# PSRAM.net
KiCad netlist of a schematic drawn in Altium Designer
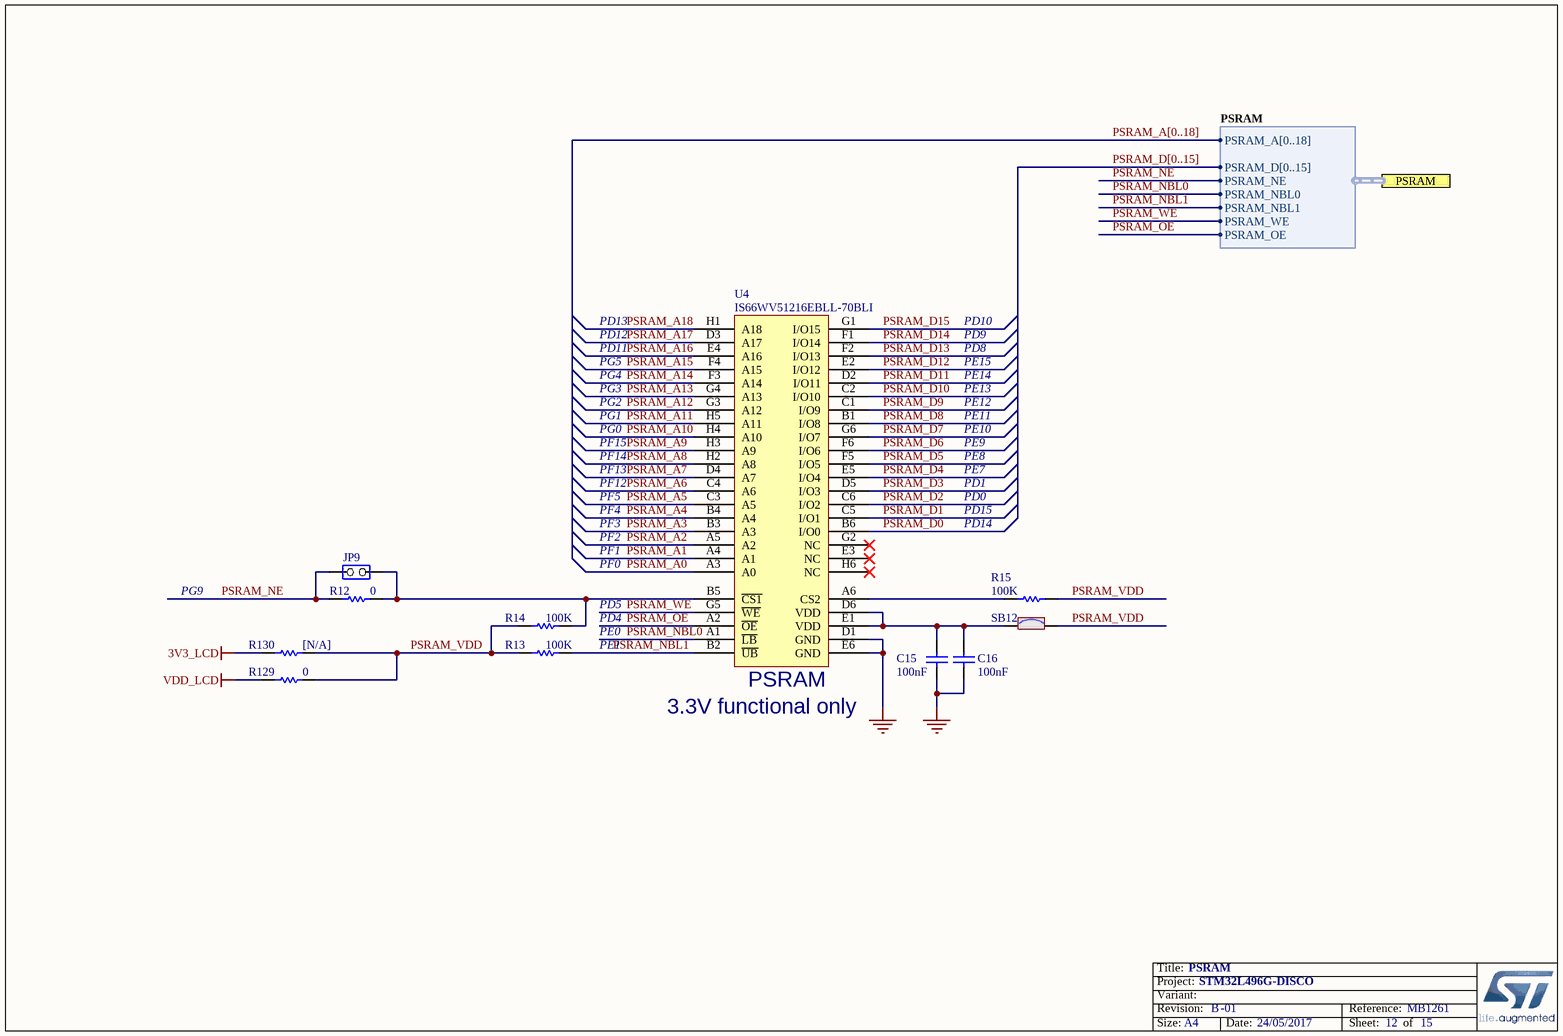
[diagram p0: PSRAM.SchDoc]

(export (version "E")
  (design (tool "Eeschema 10.0.6"))
  (components
    (comp (ref "C15")
      (value "100nF")
      (footprint "0603C")
      (description "Capacitor,100nF,10%,16V,X7R,0603,YAGEO")
      (fields (field (name "Comment") "CC0603KRX7R7BB104") (field (name "PUBLISHER") "Altium Limited"))
      (libsource (lib "Miscellaneous Devices") (part "Cap"))
    )
    (comp (ref "C16")
      (value "100nF")
      (footprint "0603C")
      (description "Capacitor,100nF,10%,16V,X7R,0603,YAGEO")
      (fields (field (name "Comment") "CC0603KRX7R7BB104") (field (name "PUBLISHER") "Altium Limited"))
      (libsource (lib "Miscellaneous Devices") (part "Cap"))
    )
    (comp (ref "JP9") (value "2 PIN Jumper") (footprint "SIP2") (libsource (lib "*") (part "JP2")))
    (comp (ref "R12")
      (value "0")
      (footprint "0603R")
      (description "Resistor, 0 ,0603,1%,YAGEO")
      (fields (field (name "PUBLISHER") "Altium Limited"))
      (libsource (lib "Miscellaneous Devices") (part "res1"))
    )
    (comp (ref "R13")
      (value "100K")
      (footprint "0603R")
      (description "Resistor,100K,0603,1%,YAGEO")
      (fields (field (name "Comment") "RC0603FR-07100KL") (field (name "PUBLISHER") "Altium Limited"))
      (libsource (lib "Miscellaneous Devices") (part "res1"))
    )
    (comp (ref "R14")
      (value "100K")
      (footprint "0603R")
      (description "Resistor,100K,0603,1%,YAGEO")
      (fields (field (name "Comment") "RC0603FR-07100KL") (field (name "PUBLISHER") "Altium Limited"))
      (libsource (lib "Miscellaneous Devices") (part "res1"))
    )
    (comp (ref "R15")
      (value "100K")
      (footprint "0603R")
      (description "Resistor,100K,0603,1%,YAGEO")
      (fields (field (name "Comment") "RC0603FR-07100KL") (field (name "PUBLISHER") "Altium Limited"))
      (libsource (lib "Miscellaneous Devices") (part "res1"))
    )
    (comp (ref "R129")
      (value "0")
      (footprint "0603R")
      (description "Resistor, 0 ,0603,1%,YAGEO")
      (fields (field (name "Comment") "RC0603JR-070RL") (field (name "PUBLISHER") "Altium Limited"))
      (libsource (lib "Miscellaneous Devices") (part "res1"))
    )
    (comp (ref "R130")
      (value "[N/A]")
      (footprint "0603R")
      (description "Resistor, 0 ,0603,1%,YAGEO")
      (fields (field (name "PUBLISHER") "Altium Limited"))
      (libsource (lib "Miscellaneous Devices") (part "res1"))
    )
    (comp (ref "SB12")
      (value "Solder Bridge ON")
      (footprint "SB_0603")
      (libsource (lib "MCD_TOOLS") (part "SB_ON"))
    )
    (comp (ref "U4")
      (value "IS66WV51216EBLL-70BLI")
      (footprint "FBGA48_0R75_6X8")
      (description "8M Bit static RAMs organized as 512K words by  16 bits.")
      (libsource (lib "Big Orga") (part "IS66WV51216EBLL-70BLI"))
    )
  )
  (nets
    (net (code "2") (name "/PSRAM_A0") (class "Default")
      (node (ref "U4") (pin "A3") (pinfunction "A0_A3") (pintype "passive"))
    )
    (net (code "3") (name "/PSRAM_A1") (class "Default")
      (node (ref "U4") (pin "A4") (pinfunction "A1_A4") (pintype "passive"))
    )
    (net (code "4") (name "/PSRAM_A2") (class "Default")
      (node (ref "U4") (pin "A5") (pinfunction "A2_A5") (pintype "passive"))
    )
    (net (code "5") (name "/PSRAM_A3") (class "Default")
      (node (ref "U4") (pin "B3") (pinfunction "A3_B3") (pintype "passive"))
    )
    (net (code "6") (name "/PSRAM_A4") (class "Default")
      (node (ref "U4") (pin "B4") (pinfunction "A4_B4") (pintype "passive"))
    )
    (net (code "7") (name "/PSRAM_A5") (class "Default")
      (node (ref "U4") (pin "C3") (pinfunction "A5_C3") (pintype "passive"))
    )
    (net (code "8") (name "/PSRAM_A6") (class "Default")
      (node (ref "U4") (pin "C4") (pinfunction "A6_C4") (pintype "passive"))
    )
    (net (code "9") (name "/PSRAM_A7") (class "Default")
      (node (ref "U4") (pin "D4") (pinfunction "A7_D4") (pintype "passive"))
    )
    (net (code "10") (name "/PSRAM_A8") (class "Default")
      (node (ref "U4") (pin "H2") (pinfunction "A8_H2") (pintype "passive"))
    )
    (net (code "11") (name "/PSRAM_A9") (class "Default")
      (node (ref "U4") (pin "H3") (pinfunction "A9_H3") (pintype "passive"))
    )
    (net (code "12") (name "/PSRAM_A10") (class "Default")
      (node (ref "U4") (pin "H4") (pinfunction "A10_H4") (pintype "passive"))
    )
    (net (code "13") (name "/PSRAM_A11") (class "Default")
      (node (ref "U4") (pin "H5") (pinfunction "A11_H5") (pintype "passive"))
    )
    (net (code "14") (name "/PSRAM_A12") (class "Default")
      (node (ref "U4") (pin "G3") (pinfunction "A12_G3") (pintype "passive"))
    )
    (net (code "15") (name "/PSRAM_A13") (class "Default")
      (node (ref "U4") (pin "G4") (pinfunction "A13_G4") (pintype "passive"))
    )
    (net (code "16") (name "/PSRAM_A14") (class "Default")
      (node (ref "U4") (pin "F3") (pinfunction "A14_F3") (pintype "passive"))
    )
    (net (code "17") (name "/PSRAM_A15") (class "Default")
      (node (ref "U4") (pin "F4") (pinfunction "A15_F4") (pintype "passive"))
    )
    (net (code "18") (name "/PSRAM_A16") (class "Default")
      (node (ref "U4") (pin "E4") (pinfunction "A16_E4") (pintype "passive"))
    )
    (net (code "19") (name "/PSRAM_A17") (class "Default")
      (node (ref "U4") (pin "D3") (pinfunction "A17_D3") (pintype "passive"))
    )
    (net (code "20") (name "/PSRAM_A18") (class "Default")
      (node (ref "U4") (pin "H1") (pinfunction "A18_H1") (pintype "passive"))
    )
    (net (code "22") (name "/PSRAM_D0") (class "Default")
      (node (ref "U4") (pin "B6") (pinfunction "I/O0_B6") (pintype "passive"))
    )
    (net (code "23") (name "/PSRAM_D1") (class "Default")
      (node (ref "U4") (pin "C5") (pinfunction "I/O1_C5") (pintype "passive"))
    )
    (net (code "24") (name "/PSRAM_D2") (class "Default")
      (node (ref "U4") (pin "C6") (pinfunction "I/O2_C6") (pintype "passive"))
    )
    (net (code "25") (name "/PSRAM_D3") (class "Default")
      (node (ref "U4") (pin "D5") (pinfunction "I/O3_D5") (pintype "passive"))
    )
    (net (code "26") (name "/PSRAM_D4") (class "Default")
      (node (ref "U4") (pin "E5") (pinfunction "I/O4_E5") (pintype "passive"))
    )
    (net (code "27") (name "/PSRAM_D5") (class "Default")
      (node (ref "U4") (pin "F5") (pinfunction "I/O5_F5") (pintype "passive"))
    )
    (net (code "28") (name "/PSRAM_D6") (class "Default")
      (node (ref "U4") (pin "F6") (pinfunction "I/O6_F6") (pintype "passive"))
    )
    (net (code "29") (name "/PSRAM_D7") (class "Default")
      (node (ref "U4") (pin "G6") (pinfunction "I/O7_G6") (pintype "passive"))
    )
    (net (code "30") (name "/PSRAM_D8") (class "Default")
      (node (ref "U4") (pin "B1") (pinfunction "I/O8_B1") (pintype "passive"))
    )
    (net (code "31") (name "/PSRAM_D9") (class "Default")
      (node (ref "U4") (pin "C1") (pinfunction "I/O9_C1") (pintype "passive"))
    )
    (net (code "32") (name "/PSRAM_D10") (class "Default")
      (node (ref "U4") (pin "C2") (pinfunction "I/O10_C2") (pintype "passive"))
    )
    (net (code "33") (name "/PSRAM_D11") (class "Default")
      (node (ref "U4") (pin "D2") (pinfunction "I/O11_D2") (pintype "passive"))
    )
    (net (code "34") (name "/PSRAM_D12") (class "Default")
      (node (ref "U4") (pin "E2") (pinfunction "I/O12_E2") (pintype "passive"))
    )
    (net (code "35") (name "/PSRAM_D13") (class "Default")
      (node (ref "U4") (pin "F2") (pinfunction "I/O13_F2") (pintype "passive"))
    )
    (net (code "36") (name "/PSRAM_D14") (class "Default")
      (node (ref "U4") (pin "F1") (pinfunction "I/O14_F1") (pintype "passive"))
    )
    (net (code "37") (name "/PSRAM_D15") (class "Default")
      (node (ref "U4") (pin "G1") (pinfunction "I/O15_G1") (pintype "passive"))
    )
    (net (code "39") (name "/PSRAM_NBL0") (class "Default")
      (node (ref "U4") (pin "A1") (pinfunction "~{LB}_A1") (pintype "passive"))
    )
    (net (code "40") (name "/PSRAM_NBL1") (class "Default")
      (node (ref "R13") (pin "1") (pinfunction "1_1") (pintype "passive"))
      (node (ref "U4") (pin "B2") (pinfunction "~{UB}_B2") (pintype "passive"))
    )
    (net (code "41") (name "/PSRAM_NE") (class "Default")
      (node (ref "JP9") (pin "1") (pinfunction "COMMON_1") (pintype "passive"))
      (node (ref "R12") (pin "2") (pinfunction "2_2") (pintype "passive"))
    )
    (net (code "42") (name "/PSRAM_OE") (class "Default")
      (node (ref "U4") (pin "A2") (pinfunction "~{OE}_A2") (pintype "passive"))
    )
    (net (code "43") (name "/PSRAM_VDD") (class "Default")
      (node (ref "R129") (pin "1") (pinfunction "1_1") (pintype "passive"))
      (node (ref "R13") (pin "2") (pinfunction "2_2") (pintype "passive"))
      (node (ref "R130") (pin "1") (pinfunction "1_1") (pintype "passive"))
      (node (ref "R14") (pin "2") (pinfunction "2_2") (pintype "passive"))
      (node (ref "R15") (pin "1") (pinfunction "1_1") (pintype "passive"))
      (node (ref "SB12") (pin "2") (pinfunction "2_2") (pintype "passive"))
    )
    (net (code "44") (name "/PSRAM_WE") (class "Default")
      (node (ref "U4") (pin "G5") (pinfunction "~{WE}_G5") (pintype "passive"))
    )
    (net (code "46") (name "3V3_LCD") (class "Default")
      (node (ref "R130") (pin "2") (pinfunction "2_2") (pintype "passive"))
    )
    (net (code "47") (name "GND") (class "Default")
      (node (ref "C15") (pin "2") (pinfunction "2_2") (pintype "passive"))
      (node (ref "C16") (pin "2") (pinfunction "2_2") (pintype "passive"))
      (node (ref "U4") (pin "D1") (pinfunction "GND_D1") (pintype "passive"))
      (node (ref "U4") (pin "E6") (pinfunction "GND_E6") (pintype "passive"))
    )
    (net (code "48") (name "Net-(C15-Pad1)") (class "Default")
      (node (ref "C15") (pin "1") (pinfunction "1_1") (pintype "passive"))
      (node (ref "C16") (pin "1") (pinfunction "1_1") (pintype "passive"))
      (node (ref "SB12") (pin "1") (pinfunction "1_1") (pintype "passive"))
      (node (ref "U4") (pin "D6") (pinfunction "VDD_D6") (pintype "passive"))
      (node (ref "U4") (pin "E1") (pinfunction "VDD_E1") (pintype "passive"))
    )
    (net (code "49") (name "Net-(JP9-NO)") (class "Default")
      (node (ref "JP9") (pin "2") (pinfunction "NO_2") (pintype "passive"))
      (node (ref "R12") (pin "1") (pinfunction "1_1") (pintype "passive"))
      (node (ref "R14") (pin "1") (pinfunction "1_1") (pintype "passive"))
      (node (ref "U4") (pin "B5") (pinfunction "~{CS1}_B5") (pintype "passive"))
    )
    (net (code "50") (name "Net-(U4-CS2)") (class "Default")
      (node (ref "R15") (pin "2") (pinfunction "2_2") (pintype "passive"))
      (node (ref "U4") (pin "A6") (pinfunction "CS2_A6") (pintype "passive"))
    )
    (net (code "51") (name "VDD_LCD") (class "Default")
      (node (ref "R129") (pin "2") (pinfunction "2_2") (pintype "passive"))
    )
    (net (code "52") (name "unconnected-(U4-NC-PadE3)") (class "Default")
      (node (ref "U4") (pin "E3") (pinfunction "NC_E3") (pintype "passive+no_connect"))
    )
    (net (code "53") (name "unconnected-(U4-NC-PadG2)") (class "Default")
      (node (ref "U4") (pin "G2") (pinfunction "NC_G2") (pintype "passive+no_connect"))
    )
    (net (code "54") (name "unconnected-(U4-NC-PadH6)") (class "Default")
      (node (ref "U4") (pin "H6") (pinfunction "NC_H6") (pintype "passive+no_connect"))
    )
  )
)
